# Motor_driver.net
KiCad netlist of a schematic drawn in Altium Designer
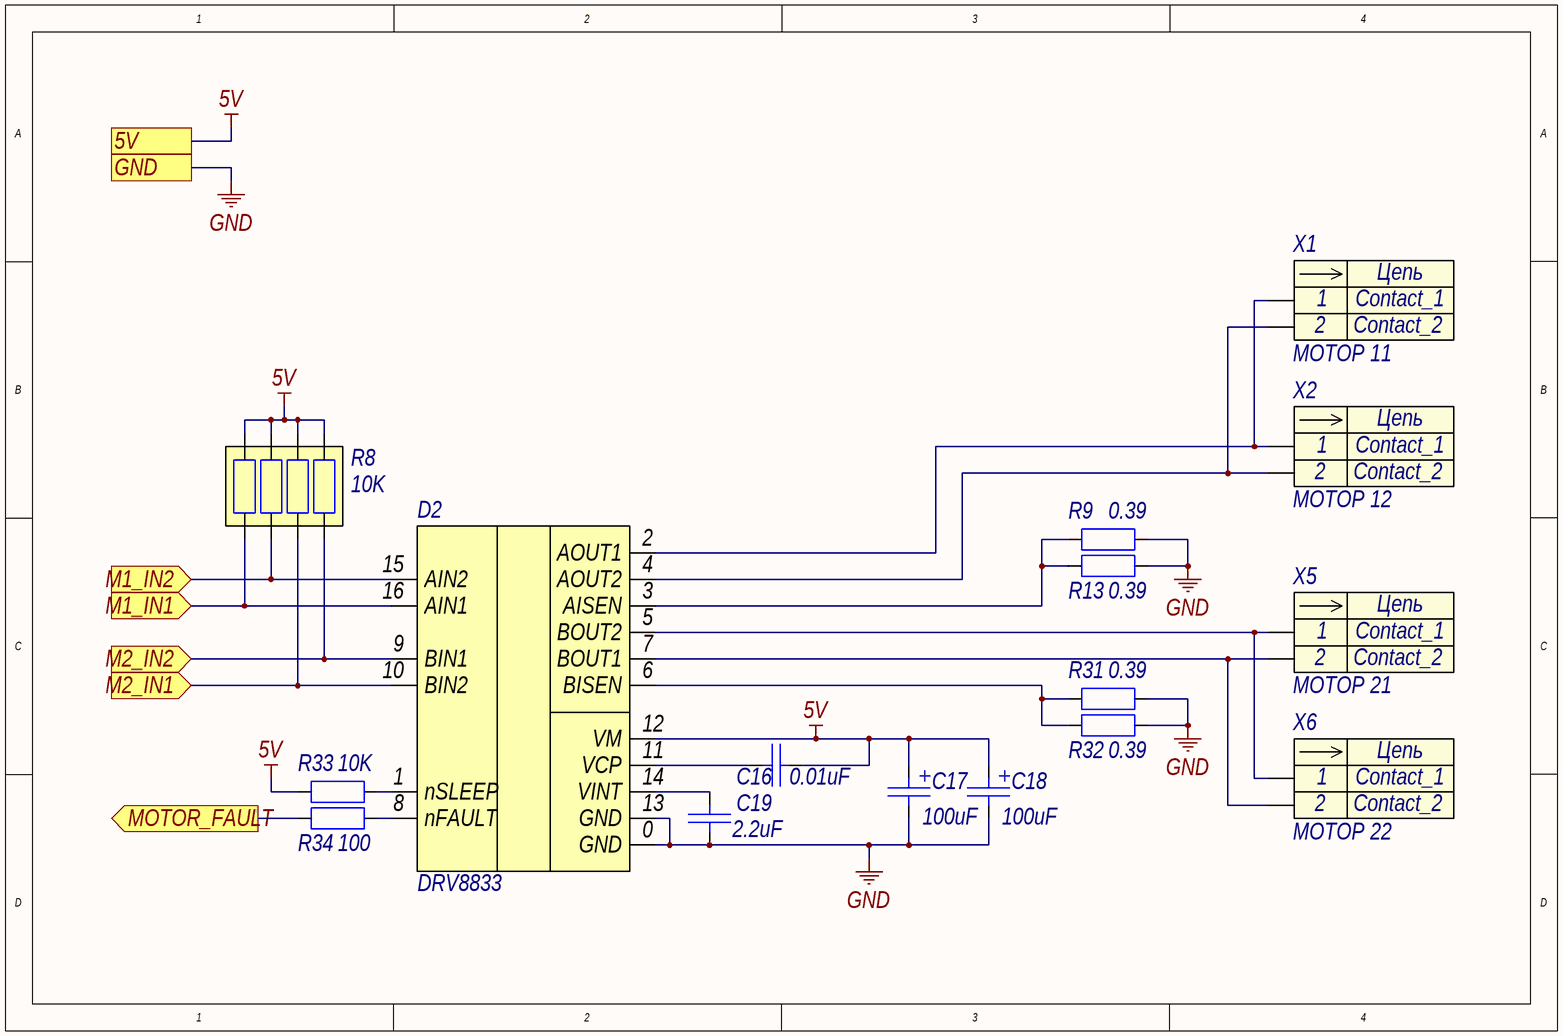
[diagram p0: Motor driver.SchDoc]

(export (version "E")
  (design (tool "Eeschema 10.0.6"))
  (components
    (comp (ref "C16")
      (value "0.01uF")
      (footprint "Footprints:NPC0805")
      (description "Nonpolarized Capacitor (Ceramic)")
      (libsource (lib "Passive") (part "Nonpolarized Capacitor"))
    )
    (comp (ref "C17")
      (value "100uF")
      (footprint "Footprints:TANTAL CAPACITOR C")
      (description "Polarized Capacitor (Electrolytic, tantalum)")
      (libsource (lib "Passive") (part "Polarized Capacitor"))
    )
    (comp (ref "C18")
      (value "100uF")
      (footprint "Footprints:TANTAL CAPACITOR C")
      (description "Polarized Capacitor (Electrolytic, tantalum)")
      (libsource (lib "Passive") (part "Polarized Capacitor"))
    )
    (comp (ref "C19")
      (value "2.2uF")
      (footprint "Footprints:NPC0805")
      (description "Nonpolarized Capacitor (Ceramic)")
      (libsource (lib "Passive") (part "Nonpolarized Capacitor"))
    )
    (comp (ref "D2")
      (value "DRV8833")
      (footprint "Footprints:TSSOP16")
      (description "DC motor driver, 2 channel,  2.7-10.8V, 1.5A")
      (libsource (lib "Miscellaneous") (part "DRV8833"))
    )
    (comp (ref "R8")
      (value "10K")
      (footprint "Footprints:CAT16")
      (description "Resistor Array")
      (libsource (lib "Passive") (part "Resistor Array"))
    )
    (comp (ref "R9")
      (value "0.39")
      (footprint "Footprints:R2512")
      (description "Resistor")
      (libsource (lib "Passive") (part "Resistor"))
    )
    (comp (ref "R13")
      (value "0.39")
      (footprint "Footprints:R2512")
      (description "Resistor")
      (libsource (lib "Passive") (part "Resistor"))
    )
    (comp (ref "R31")
      (value "0.39")
      (footprint "Footprints:R2512")
      (description "Resistor")
      (libsource (lib "Passive") (part "Resistor"))
    )
    (comp (ref "R32")
      (value "0.39")
      (footprint "Footprints:R2512")
      (description "Resistor")
      (libsource (lib "Passive") (part "Resistor"))
    )
    (comp (ref "R33")
      (value "10K")
      (footprint "Footprints:R0805")
      (description "Resistor")
      (libsource (lib "") (part "Resistor_1"))
    )
    (comp (ref "R34")
      (value "100")
      (footprint "Footprints:R0805")
      (description "Resistor")
      (libsource (lib "") (part "Resistor_1"))
    )
    (comp (ref "X1")
      (value "МОТОР 11")
      (footprint "Footprints:KLS2-301-5.00 WITH LABEL")
      (description "Header 2 pin")
      (libsource (lib "Mechanical") (part "Header 2 pin"))
    )
    (comp (ref "X2")
      (value "МОТОР 12")
      (footprint "Footprints:KLS2-301-5.00 WITH LABEL")
      (description "Header 2 pin")
      (libsource (lib "Mechanical") (part "Header 2 pin"))
    )
    (comp (ref "X5")
      (value "МОТОР 21")
      (footprint "Footprints:KLS2-301-5.00 WITH LABEL")
      (description "Header 2 pin")
      (libsource (lib "Mechanical") (part "Header 2 pin"))
    )
    (comp (ref "X6")
      (value "МОТОР 22")
      (footprint "Footprints:KLS2-301-5.00 WITH LABEL")
      (description "Header 2 pin")
      (libsource (lib "Mechanical") (part "Header 2 pin"))
    )
  )
  (nets
    (net (code "1") (name "/M1_IN1") (class "Default")
      (node (ref "D2") (pin "16") (pinfunction "AIN1_16") (pintype "passive"))
      (node (ref "R8") (pin "1") (pinfunction "1_1") (pintype "passive"))
    )
    (net (code "2") (name "/M1_IN2") (class "Default")
      (node (ref "D2") (pin "15") (pinfunction "AIN2_15") (pintype "passive"))
      (node (ref "R8") (pin "2") (pinfunction "2_2") (pintype "passive"))
    )
    (net (code "3") (name "/M2_IN1") (class "Default")
      (node (ref "D2") (pin "10") (pinfunction "BIN2_10") (pintype "passive"))
      (node (ref "R8") (pin "3") (pinfunction "3_3") (pintype "passive"))
    )
    (net (code "4") (name "/M2_IN2") (class "Default")
      (node (ref "D2") (pin "9") (pinfunction "BIN1_9") (pintype "passive"))
      (node (ref "R8") (pin "4") (pinfunction "4_4") (pintype "passive"))
    )
    (net (code "5") (name "/MOTOR_FAULT") (class "Default")
      (node (ref "R34") (pin "2") (pinfunction "2_2") (pintype "passive"))
    )
    (net (code "6") (name "5V") (class "Default")
      (node (ref "C16") (pin "1") (pinfunction "1_1") (pintype "passive"))
      (node (ref "C17") (pin "1") (pinfunction "1_1") (pintype "passive"))
      (node (ref "C18") (pin "1") (pinfunction "1_1") (pintype "passive"))
      (node (ref "D2") (pin "12") (pinfunction "VM_12") (pintype "passive"))
      (node (ref "R33") (pin "2") (pinfunction "2_2") (pintype "passive"))
      (node (ref "R8") (pin "5") (pinfunction "5_5") (pintype "passive"))
      (node (ref "R8") (pin "6") (pinfunction "6_6") (pintype "passive"))
      (node (ref "R8") (pin "7") (pinfunction "7_7") (pintype "passive"))
      (node (ref "R8") (pin "8") (pinfunction "8_8") (pintype "passive"))
    )
    (net (code "7") (name "GND") (class "Default")
      (node (ref "C17") (pin "2") (pinfunction "2_2") (pintype "passive"))
      (node (ref "C18") (pin "2") (pinfunction "2_2") (pintype "passive"))
      (node (ref "C19") (pin "1") (pinfunction "1_1") (pintype "passive"))
      (node (ref "D2") (pin "0") (pinfunction "GND_0") (pintype "passive"))
      (node (ref "D2") (pin "13") (pinfunction "GND_13") (pintype "passive"))
      (node (ref "R13") (pin "2") (pinfunction "2_2") (pintype "passive"))
      (node (ref "R31") (pin "2") (pinfunction "2_2") (pintype "passive"))
      (node (ref "R32") (pin "2") (pinfunction "2_2") (pintype "passive"))
      (node (ref "R9") (pin "2") (pinfunction "2_2") (pintype "passive"))
    )
    (net (code "8") (name "Net-(D2-AISEN)") (class "Default")
      (node (ref "D2") (pin "3") (pinfunction "AISEN_3") (pintype "passive"))
      (node (ref "R13") (pin "1") (pinfunction "1_1") (pintype "passive"))
      (node (ref "R9") (pin "1") (pinfunction "1_1") (pintype "passive"))
    )
    (net (code "9") (name "Net-(D2-AOUT1)") (class "Default")
      (node (ref "D2") (pin "2") (pinfunction "AOUT1_2") (pintype "passive"))
      (node (ref "X1") (pin "1") (pinfunction "1_1") (pintype "passive"))
      (node (ref "X2") (pin "1") (pinfunction "1_1") (pintype "passive"))
    )
    (net (code "10") (name "Net-(D2-AOUT2)") (class "Default")
      (node (ref "D2") (pin "4") (pinfunction "AOUT2_4") (pintype "passive"))
      (node (ref "X1") (pin "2") (pinfunction "2_2") (pintype "passive"))
      (node (ref "X2") (pin "2") (pinfunction "2_2") (pintype "passive"))
    )
    (net (code "11") (name "Net-(D2-BISEN)") (class "Default")
      (node (ref "D2") (pin "6") (pinfunction "BISEN_6") (pintype "passive"))
      (node (ref "R31") (pin "1") (pinfunction "1_1") (pintype "passive"))
      (node (ref "R32") (pin "1") (pinfunction "1_1") (pintype "passive"))
    )
    (net (code "12") (name "Net-(D2-BOUT1)") (class "Default")
      (node (ref "D2") (pin "7") (pinfunction "BOUT1_7") (pintype "passive"))
      (node (ref "X5") (pin "2") (pinfunction "2_2") (pintype "passive"))
      (node (ref "X6") (pin "2") (pinfunction "2_2") (pintype "passive"))
    )
    (net (code "13") (name "Net-(D2-BOUT2)") (class "Default")
      (node (ref "D2") (pin "5") (pinfunction "BOUT2_5") (pintype "passive"))
      (node (ref "X5") (pin "1") (pinfunction "1_1") (pintype "passive"))
      (node (ref "X6") (pin "1") (pinfunction "1_1") (pintype "passive"))
    )
    (net (code "14") (name "Net-(D2-VCP)") (class "Default")
      (node (ref "C16") (pin "2") (pinfunction "2_2") (pintype "passive"))
      (node (ref "D2") (pin "11") (pinfunction "VCP_11") (pintype "passive"))
    )
    (net (code "15") (name "Net-(D2-VINT)") (class "Default")
      (node (ref "C19") (pin "2") (pinfunction "2_2") (pintype "passive"))
      (node (ref "D2") (pin "14") (pinfunction "VINT_14") (pintype "passive"))
    )
    (net (code "16") (name "Net-(D2-nFAULT)") (class "Default")
      (node (ref "D2") (pin "8") (pinfunction "nFAULT_8") (pintype "passive"))
      (node (ref "R34") (pin "1") (pinfunction "1_1") (pintype "passive"))
    )
    (net (code "17") (name "Net-(D2-nSLEEP)") (class "Default")
      (node (ref "D2") (pin "1") (pinfunction "nSLEEP_1") (pintype "passive"))
      (node (ref "R33") (pin "1") (pinfunction "1_1") (pintype "passive"))
    )
  )
)
